# olive-scanner.net
KiCad netlist of a schematic drawn in EAGLE
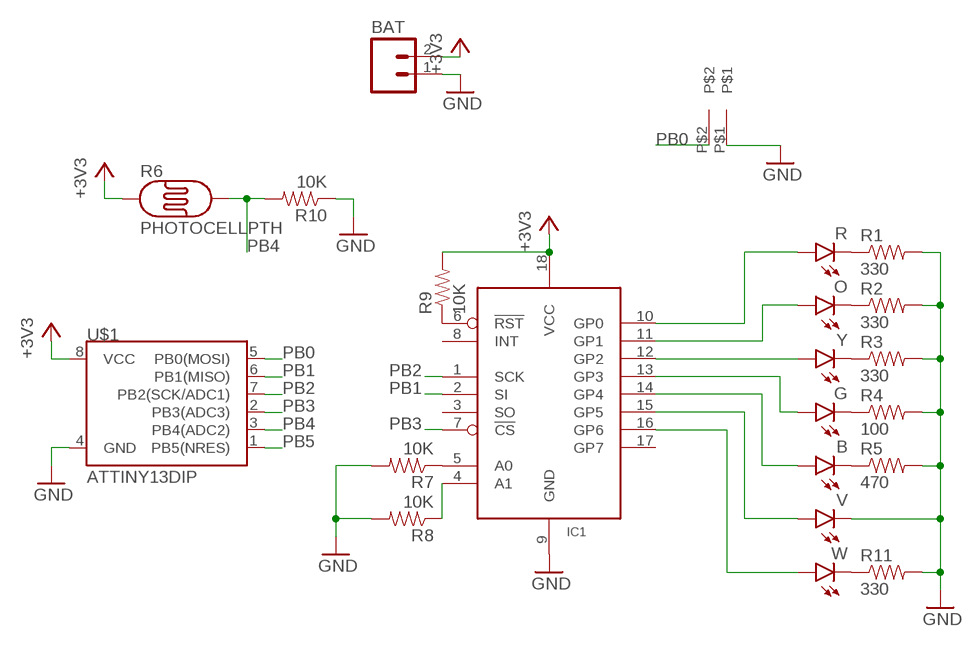
[diagram p0: schematic, sheet 1]

(export (version "E")
  (design (tool "Eeschema 10.0.6"))
  (components
    (comp (ref "B")
      (value "LED5MM")
      (footprint "eagle-import:LED5MM")
      (libsource (lib "eagle-import") (part "LED5MM"))
    )
    (comp (ref "BAT")
      (value "M02LOCK")
      (footprint "eagle-import:1X02_LOCK")
      (libsource (lib "eagle-import") (part "M02LOCK"))
    )
    (comp (ref "G")
      (value "LED5MM")
      (footprint "eagle-import:LED5MM")
      (libsource (lib "eagle-import") (part "LED5MM"))
    )
    (comp (ref "IC1")
      (value "MCP23S08/P")
      (footprint "eagle-import:DIL18")
      (libsource (lib "eagle-import") (part "MCP23S08/P"))
    )
    (comp (ref "O")
      (value "LED5MM")
      (footprint "eagle-import:LED5MM")
      (libsource (lib "eagle-import") (part "LED5MM"))
    )
    (comp (ref "R")
      (value "LED5MM")
      (footprint "eagle-import:LED5MM")
      (libsource (lib "eagle-import") (part "LED5MM"))
    )
    (comp (ref "R1")
      (value "330")
      (footprint "eagle-import:AXIAL-0.3")
      (libsource (lib "eagle-import") (part "1KOHM-1/4W-5%(PTH)"))
    )
    (comp (ref "R2")
      (value "330")
      (footprint "eagle-import:AXIAL-0.3")
      (libsource (lib "eagle-import") (part "1KOHM-1/4W-5%(PTH)"))
    )
    (comp (ref "R3")
      (value "330")
      (footprint "eagle-import:AXIAL-0.3")
      (libsource (lib "eagle-import") (part "1KOHM-1/4W-5%(PTH)"))
    )
    (comp (ref "R4")
      (value "100")
      (footprint "eagle-import:AXIAL-0.3")
      (libsource (lib "eagle-import") (part "1KOHM-1/4W-5%(PTH)"))
    )
    (comp (ref "R5")
      (value "470")
      (footprint "eagle-import:AXIAL-0.3")
      (libsource (lib "eagle-import") (part "1KOHM-1/4W-5%(PTH)"))
    )
    (comp (ref "R6")
      (value "PHOTOCELLPTH")
      (footprint "eagle-import:PHOTOCELL")
      (libsource (lib "eagle-import") (part "PHOTOCELLPTH"))
    )
    (comp (ref "R7")
      (value "10K")
      (footprint "eagle-import:AXIAL-0.3")
      (libsource (lib "eagle-import") (part "1KOHM-1/4W-5%(PTH)"))
    )
    (comp (ref "R8")
      (value "10K")
      (footprint "eagle-import:AXIAL-0.3")
      (libsource (lib "eagle-import") (part "1KOHM-1/4W-5%(PTH)"))
    )
    (comp (ref "R9")
      (value "10K")
      (footprint "eagle-import:AXIAL-0.3")
      (libsource (lib "eagle-import") (part "1KOHM-1/4W-5%(PTH)"))
    )
    (comp (ref "R10")
      (value "10K")
      (footprint "eagle-import:AXIAL-0.3")
      (libsource (lib "eagle-import") (part "1KOHM-1/4W-5%(PTH)"))
    )
    (comp (ref "R11")
      (value "330")
      (footprint "eagle-import:AXIAL-0.3")
      (libsource (lib "eagle-import") (part "1KOHM-1/4W-5%(PTH)"))
    )
    (comp (ref "U$1")
      (value "ATTINY13DIP")
      (footprint "eagle-import:DIP08")
      (libsource (lib "eagle-import") (part "ATTINY13DIP"))
    )
    (comp (ref "U$2")
      (value "PHONE_VIBRATOR")
      (footprint "eagle-import:PHONE_VIBRATOR")
      (libsource (lib "eagle-import") (part "PHONE_VIBRATOR"))
    )
    (comp (ref "V")
      (value "LED5MM")
      (footprint "eagle-import:LED5MM")
      (libsource (lib "eagle-import") (part "LED5MM"))
    )
    (comp (ref "W")
      (value "LED5MM")
      (footprint "eagle-import:LED5MM")
      (libsource (lib "eagle-import") (part "LED5MM"))
    )
    (comp (ref "Y")
      (value "LED5MM")
      (footprint "eagle-import:LED5MM")
      (libsource (lib "eagle-import") (part "LED5MM"))
    )
  )
  (nets
    (net (code "1") (name "+3V3") (class "Default")
      (node (ref "BAT") (pin "2") (pinfunction "2_2") (pintype "passive"))
      (node (ref "IC1") (pin "18") (pinfunction "VCC_18") (pintype "power_in"))
      (node (ref "R6") (pin "1") (pinfunction "P$1_1") (pintype "bidirectional"))
      (node (ref "R9") (pin "P$2") (pinfunction "2_P$2") (pintype "passive"))
      (node (ref "U$1") (pin "8") (pinfunction "VCC_8") (pintype "bidirectional"))
    )
    (net (code "2") (name "/PB0") (class "Default")
      (node (ref "U$1") (pin "5") (pinfunction "PB0(MOSI)_5") (pintype "bidirectional"))
      (node (ref "U$2") (pin "P$2") (pinfunction "P$2_P$2") (pintype "power_in"))
    )
    (net (code "3") (name "/PB1") (class "Default")
      (node (ref "IC1") (pin "2") (pinfunction "SI_2") (pintype "bidirectional"))
      (node (ref "U$1") (pin "6") (pinfunction "PB1(MISO)_6") (pintype "bidirectional"))
    )
    (net (code "4") (name "/PB2") (class "Default")
      (node (ref "IC1") (pin "1") (pinfunction "SCK_1") (pintype "input"))
      (node (ref "U$1") (pin "7") (pinfunction "PB2(SCK/ADC1)_7") (pintype "bidirectional"))
    )
    (net (code "5") (name "/PB3") (class "Default")
      (node (ref "IC1") (pin "7") (pinfunction "~{CS}_7") (pintype "input"))
      (node (ref "U$1") (pin "2") (pinfunction "PB3(ADC3)_2") (pintype "bidirectional"))
    )
    (net (code "6") (name "/PB4") (class "Default")
      (node (ref "R10") (pin "P$2") (pinfunction "2_P$2") (pintype "passive"))
      (node (ref "R6") (pin "2") (pinfunction "P$2_2") (pintype "bidirectional"))
      (node (ref "U$1") (pin "3") (pinfunction "PB4(ADC2)_3") (pintype "bidirectional"))
    )
    (net (code "7") (name "/PB5") (class "Default")
      (node (ref "U$1") (pin "1") (pinfunction "PB5(NRES)_1") (pintype "bidirectional"))
    )
    (net (code "8") (name "GND") (class "Default")
      (node (ref "BAT") (pin "1") (pinfunction "1_1") (pintype "passive"))
      (node (ref "IC1") (pin "9") (pinfunction "GND_9") (pintype "power_in"))
      (node (ref "R1") (pin "P$2") (pinfunction "2_P$2") (pintype "passive"))
      (node (ref "R10") (pin "P$1") (pinfunction "1_P$1") (pintype "passive"))
      (node (ref "R11") (pin "P$2") (pinfunction "2_P$2") (pintype "passive"))
      (node (ref "R2") (pin "P$2") (pinfunction "2_P$2") (pintype "passive"))
      (node (ref "R3") (pin "P$2") (pinfunction "2_P$2") (pintype "passive"))
      (node (ref "R4") (pin "P$2") (pinfunction "2_P$2") (pintype "passive"))
      (node (ref "R5") (pin "P$2") (pinfunction "2_P$2") (pintype "passive"))
      (node (ref "R7") (pin "P$2") (pinfunction "2_P$2") (pintype "passive"))
      (node (ref "R8") (pin "P$2") (pinfunction "2_P$2") (pintype "passive"))
      (node (ref "U$1") (pin "4") (pinfunction "GND_4") (pintype "bidirectional"))
      (node (ref "U$2") (pin "P$1") (pinfunction "P$1_P$1") (pintype "power_in"))
      (node (ref "V") (pin "K") (pinfunction "C_K") (pintype "passive"))
    )
    (net (code "9") (name "Net-(B-C)") (class "Default")
      (node (ref "B") (pin "K") (pinfunction "C_K") (pintype "passive"))
      (node (ref "R5") (pin "P$1") (pinfunction "1_P$1") (pintype "passive"))
    )
    (net (code "10") (name "Net-(G-C)") (class "Default")
      (node (ref "G") (pin "K") (pinfunction "C_K") (pintype "passive"))
      (node (ref "R4") (pin "P$1") (pinfunction "1_P$1") (pintype "passive"))
    )
    (net (code "11") (name "Net-(IC1-A0)") (class "Default")
      (node (ref "IC1") (pin "5") (pinfunction "A0_5") (pintype "input"))
      (node (ref "R7") (pin "P$1") (pinfunction "1_P$1") (pintype "passive"))
    )
    (net (code "12") (name "Net-(IC1-A1)") (class "Default")
      (node (ref "IC1") (pin "4") (pinfunction "A1_4") (pintype "input"))
      (node (ref "R8") (pin "P$1") (pinfunction "1_P$1") (pintype "passive"))
    )
    (net (code "13") (name "Net-(IC1-GP0)") (class "Default")
      (node (ref "IC1") (pin "10") (pinfunction "GP0_10") (pintype "bidirectional"))
      (node (ref "R") (pin "A") (pinfunction "A_A") (pintype "passive"))
    )
    (net (code "14") (name "Net-(IC1-GP1)") (class "Default")
      (node (ref "IC1") (pin "11") (pinfunction "GP1_11") (pintype "bidirectional"))
      (node (ref "O") (pin "A") (pinfunction "A_A") (pintype "passive"))
    )
    (net (code "15") (name "Net-(IC1-GP2)") (class "Default")
      (node (ref "IC1") (pin "12") (pinfunction "GP2_12") (pintype "bidirectional"))
      (node (ref "Y") (pin "A") (pinfunction "A_A") (pintype "passive"))
    )
    (net (code "16") (name "Net-(IC1-GP3)") (class "Default")
      (node (ref "G") (pin "A") (pinfunction "A_A") (pintype "passive"))
      (node (ref "IC1") (pin "13") (pinfunction "GP3_13") (pintype "bidirectional"))
    )
    (net (code "17") (name "Net-(IC1-GP4)") (class "Default")
      (node (ref "B") (pin "A") (pinfunction "A_A") (pintype "passive"))
      (node (ref "IC1") (pin "14") (pinfunction "GP4_14") (pintype "bidirectional"))
    )
    (net (code "18") (name "Net-(IC1-GP5)") (class "Default")
      (node (ref "IC1") (pin "15") (pinfunction "GP5_15") (pintype "bidirectional"))
      (node (ref "V") (pin "A") (pinfunction "A_A") (pintype "passive"))
    )
    (net (code "19") (name "Net-(IC1-GP6)") (class "Default")
      (node (ref "IC1") (pin "16") (pinfunction "GP6_16") (pintype "bidirectional"))
      (node (ref "W") (pin "A") (pinfunction "A_A") (pintype "passive"))
    )
    (net (code "20") (name "Net-(IC1-~{RST})") (class "Default")
      (node (ref "IC1") (pin "6") (pinfunction "~{RST}_6") (pintype "input"))
      (node (ref "R9") (pin "P$1") (pinfunction "1_P$1") (pintype "passive"))
    )
    (net (code "21") (name "Net-(O-C)") (class "Default")
      (node (ref "O") (pin "K") (pinfunction "C_K") (pintype "passive"))
      (node (ref "R2") (pin "P$1") (pinfunction "1_P$1") (pintype "passive"))
    )
    (net (code "22") (name "Net-(R-C)") (class "Default")
      (node (ref "R") (pin "K") (pinfunction "C_K") (pintype "passive"))
      (node (ref "R1") (pin "P$1") (pinfunction "1_P$1") (pintype "passive"))
    )
    (net (code "23") (name "Net-(R3-1)") (class "Default")
      (node (ref "R3") (pin "P$1") (pinfunction "1_P$1") (pintype "passive"))
      (node (ref "Y") (pin "K") (pinfunction "C_K") (pintype "passive"))
    )
    (net (code "24") (name "Net-(R11-1)") (class "Default")
      (node (ref "R11") (pin "P$1") (pinfunction "1_P$1") (pintype "passive"))
      (node (ref "W") (pin "K") (pinfunction "C_K") (pintype "passive"))
    )
    (net (code "25") (name "unconnected-(IC1-GP7-Pad17)") (class "Default")
      (node (ref "IC1") (pin "17") (pinfunction "GP7_17") (pintype "bidirectional"))
    )
    (net (code "26") (name "unconnected-(IC1-INT-Pad8)") (class "Default")
      (node (ref "IC1") (pin "8") (pinfunction "INT_8") (pintype "output"))
    )
    (net (code "27") (name "unconnected-(IC1-SO-Pad3)") (class "Default")
      (node (ref "IC1") (pin "3") (pinfunction "SO_3") (pintype "input"))
    )
  )
)
